# TSAL.net
KiCad netlist of a schematic drawn in Altium Designer
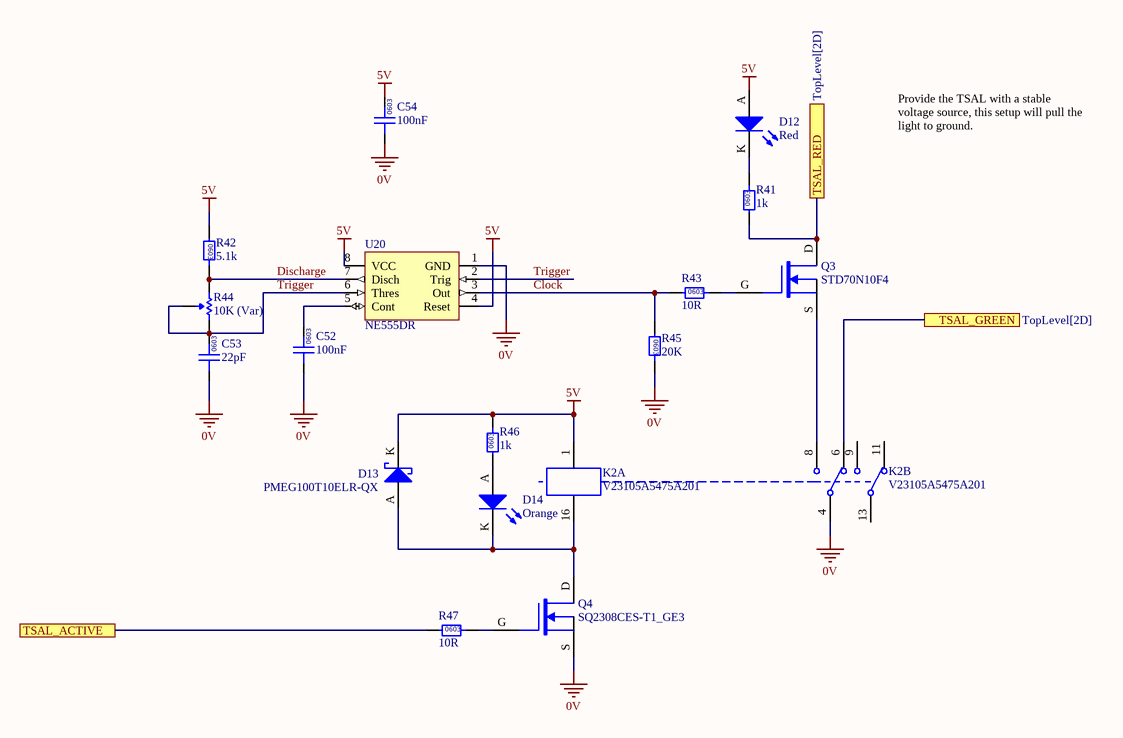
[diagram p0: TSAL.SchDoc]

(export (version "E")
  (design (tool "Eeschema 10.0.6"))
  (components
    (comp (ref "C52")
      (value "100nF")
      (footprint "0603")
      (fields
        (field (name "PART NUMBER") "GCM188L81H104KA57D")
        (field (name "MANUFACTURER") "muRata")
        (field (name "TOLERANCE") "±10%")
      )
      (libsource (lib "ts_standard_library") (part "Capacitor 0603"))
    )
    (comp (ref "C53")
      (value "22pF")
      (footprint "0603")
      (fields
        (field (name "PART NUMBER") "GRM0335C1H220JA01D")
        (field (name "MANUFACTURER") "Murata Electronics")
        (field (name "TOLERANCE") "±5%")
      )
      (libsource (lib "ts_standard_library") (part "Capacitor 0603"))
    )
    (comp (ref "C54")
      (value "100nF")
      (footprint "0603")
      (fields
        (field (name "PART NUMBER") "GCM188L81H104KA57D")
        (field (name "MANUFACTURER") "muRata")
        (field (name "TOLERANCE") "±10%")
      )
      (libsource (lib "ts_standard_library") (part "Capacitor 0603"))
    )
    (comp (ref "D12")
      (value "Red")
      (footprint "0805 LED")
      (description "Red LED Indication - Discrete 1.75V 0805 (2012 Metric)")
      (fields (field (name "PART NUMBER") "SML-210LTT86") (field (name "MANUFACTURER") "ROHM Semiconductor"))
      (libsource (lib "ts_standard_library") (part "LED"))
    )
    (comp (ref "D13")
      (value "PMEG100T10ELR-QX")
      (footprint "NXP SOD123W")
      (fields
        (field (name "MANUFACTURER") "Nexperia USA Inc.")
        (field (name "DIGIKEY PART NUMBER") "1727-PMEG100T10ELR-QXCT-ND")
      )
      (libsource (lib "ts_standard_library") (part "Diode (Schottky)"))
    )
    (comp (ref "D14")
      (value "Orange")
      (footprint "0805 LED")
      (description "Orange LED Indication - Discrete 1.75V 0805 (2012 Metric)")
      (fields (field (name "PART NUMBER") "SML-211DTT86") (field (name "MANUFACTURER") "ROHM Semiconductor"))
      (libsource (lib "ts_standard_library") (part "LED"))
    )
    (comp (ref "K2")
      (value "V23105A5475A201")
      (footprint "TI 2-DIL")
      (description "5V DPDT Relay 3A 220VDC")
      (libsource (lib "Team Swinburne") (part "Symbol"))
    )
    (comp (ref "Q3")
      (value "STD70N10F4")
      (footprint "STM TO-252 MOSFET")
      (description "N-Channel 100V 60A (Tc) 125W (Tc) Surface Mount DPAK")
      (fields
        (field (name "MANUFACTURER") "STMicroelectronics")
        (field (name "DIGIKEY PART NUMBER") "497-8806-2-ND")
        (field (name "PUBLISHER") "Altium Limited")
      )
      (libsource (lib "ts_standard_library") (part "MOSFET-N"))
    )
    (comp (ref "Q4")
      (value "SQ2308CES-T1_GE3")
      (footprint "VSHY SOT-23-3")
      (description "MOSFET N-CH 60V 2.3A SOT23")
      (fields
        (field (name "MANUFACTURER") "Vishay Siliconix")
        (field (name "DIGIKEY PART NUMBER") "SQ2308CES-T1_GE3CT-ND")
        (field (name "PUBLISHER") "Altium Limited")
      )
      (libsource (lib "ts_standard_library") (part "MOSFET-N"))
    )
    (comp (ref "R41")
      (value "1k")
      (footprint "0603")
      (fields
        (field (name "PART NUMBER") "RC0603FR-071KL")
        (field (name "MANUFACTURER") "YAGEO")
        (field (name "TOLERANCE") "0.01")
      )
      (libsource (lib "ts_standard_library") (part "Resistor 0603"))
    )
    (comp (ref "R42")
      (value "5.1k")
      (footprint "0603")
      (fields
        (field (name "PART NUMBER") "RC0603JR-075K1L")
        (field (name "MANUFACTURER") "YAGEO")
        (field (name "TOLERANCE") "0.01")
      )
      (libsource (lib "ts_standard_library") (part "Resistor 0603"))
    )
    (comp (ref "R43")
      (value "10R")
      (footprint "0603")
      (fields
        (field (name "PART NUMBER") "RC0603FR-0710RL")
        (field (name "MANUFACTURER") "YAGEO")
        (field (name "TOLERANCE") "0.01")
      )
      (libsource (lib "ts_standard_library") (part "Resistor 0603"))
    )
    (comp (ref "R44")
      (value "10K (Var)")
      (footprint "B 3296")
      (fields
        (field (name "PART NUMBER") "3296W-1-103LF")
        (field (name "MANUFACTURER") "Bournes Inc")
        (field (name "TOLERANCE") "0.1")
      )
      (libsource (lib "ts_standard_library") (part "Resistor (Potentiometer)"))
    )
    (comp (ref "R45")
      (value "20K")
      (footprint "0603")
      (fields
        (field (name "PART NUMBER") "RC0603FR-0720KL")
        (field (name "MANUFACTURER") "YAGEO")
        (field (name "TOLERANCE") "0.01")
      )
      (libsource (lib "ts_standard_library") (part "Resistor 0603"))
    )
    (comp (ref "R46")
      (value "1k")
      (footprint "0603")
      (fields
        (field (name "PART NUMBER") "RC0603FR-071KL")
        (field (name "MANUFACTURER") "YAGEO")
        (field (name "TOLERANCE") "0.01")
      )
      (libsource (lib "ts_standard_library") (part "Resistor 0603"))
    )
    (comp (ref "R47")
      (value "10R")
      (footprint "0603")
      (fields
        (field (name "PART NUMBER") "RC0603FR-0710RL")
        (field (name "MANUFACTURER") "YAGEO")
        (field (name "TOLERANCE") "0.01")
      )
      (libsource (lib "ts_standard_library") (part "Resistor 0603"))
    )
    (comp (ref "U20")
      (value "NE555DR")
      (footprint "TI 8-SOIC")
      (description "IC OSC SGL TIMER 100KHZ 8-SOIC")
      (libsource (lib "Team Swinburne") (part "NE555DR"))
    )
  )
  (nets
    (net (code "1") (name "/Clock") (class "Default")
      (node (ref "R43") (pin "1") (pinfunction "1_1") (pintype "passive"))
      (node (ref "R45") (pin "1") (pinfunction "1_1") (pintype "passive"))
      (node (ref "U20") (pin "3") (pinfunction "Out_3") (pintype "output"))
    )
    (net (code "2") (name "/Discharge") (class "Default")
      (node (ref "R42") (pin "2") (pinfunction "2_2") (pintype "passive"))
      (node (ref "R44") (pin "3") (pinfunction "CW_3") (pintype "passive"))
      (node (ref "U20") (pin "7") (pinfunction "Disch_7") (pintype "output"))
    )
    (net (code "3") (name "/TSAL_ACTIVE") (class "Default")
      (node (ref "R47") (pin "1") (pinfunction "1_1") (pintype "passive"))
    )
    (net (code "4") (name "/TSAL_GREEN") (class "Default")
      (node (ref "K2") (pin "6") (pinfunction "6_6") (pintype "passive"))
    )
    (net (code "5") (name "/TSAL_RED") (class "Default")
      (node (ref "Q3") (pin "D") (pinfunction "D_D") (pintype "passive"))
      (node (ref "R41") (pin "1") (pinfunction "1_1") (pintype "passive"))
    )
    (net (code "6") (name "/Trigger") (class "Default")
      (node (ref "C53") (pin "2") (pinfunction "2_2") (pintype "passive"))
      (node (ref "R44") (pin "1") (pinfunction "CCW_1") (pintype "passive"))
      (node (ref "R44") (pin "2") (pinfunction "Wiper_2") (pintype "passive"))
      (node (ref "U20") (pin "2") (pinfunction "Trig_2") (pintype "input"))
      (node (ref "U20") (pin "6") (pinfunction "Thres_6") (pintype "input"))
    )
    (net (code "7") (name "0V") (class "Default")
      (node (ref "C52") (pin "1") (pinfunction "1_1") (pintype "passive"))
      (node (ref "C53") (pin "1") (pinfunction "1_1") (pintype "passive"))
      (node (ref "C54") (pin "1") (pinfunction "1_1") (pintype "passive"))
      (node (ref "K2") (pin "4") (pinfunction "4_4") (pintype "passive"))
      (node (ref "Q4") (pin "S") (pinfunction "S_S") (pintype "passive"))
      (node (ref "R45") (pin "2") (pinfunction "2_2") (pintype "passive"))
      (node (ref "U20") (pin "1") (pinfunction "GND_1") (pintype "power_in"))
    )
    (net (code "8") (name "5V") (class "Default")
      (node (ref "C54") (pin "2") (pinfunction "2_2") (pintype "passive"))
      (node (ref "D12") (pin "A") (pinfunction "A_A") (pintype "passive"))
      (node (ref "D13") (pin "K") (pinfunction "K_K") (pintype "passive"))
      (node (ref "K2") (pin "1") (pinfunction "1_1") (pintype "passive"))
      (node (ref "R42") (pin "1") (pinfunction "1_1") (pintype "passive"))
      (node (ref "R46") (pin "2") (pinfunction "2_2") (pintype "passive"))
      (node (ref "U20") (pin "4") (pinfunction "Reset_4") (pintype "passive"))
      (node (ref "U20") (pin "8") (pinfunction "VCC_8") (pintype "passive"))
    )
    (net (code "9") (name "Net-(D12-PadK)") (class "Default")
      (node (ref "D12") (pin "K") (pinfunction "K_K") (pintype "passive"))
      (node (ref "R41") (pin "2") (pinfunction "2_2") (pintype "passive"))
    )
    (net (code "10") (name "Net-(D13-PadA)") (class "Default")
      (node (ref "D13") (pin "A") (pinfunction "A_A") (pintype "passive"))
      (node (ref "D14") (pin "K") (pinfunction "K_K") (pintype "passive"))
      (node (ref "K2") (pin "16") (pinfunction "16_16") (pintype "passive"))
      (node (ref "Q4") (pin "D") (pinfunction "D_D") (pintype "passive"))
    )
    (net (code "11") (name "Net-(D14-PadA)") (class "Default")
      (node (ref "D14") (pin "A") (pinfunction "A_A") (pintype "passive"))
      (node (ref "R46") (pin "1") (pinfunction "1_1") (pintype "passive"))
    )
    (net (code "12") (name "Net-(K2-Pad8)") (class "Default")
      (node (ref "K2") (pin "8") (pinfunction "8_8") (pintype "passive"))
      (node (ref "Q3") (pin "S") (pinfunction "S_S") (pintype "passive"))
    )
    (net (code "13") (name "Net-(Q3-PadG)") (class "Default")
      (node (ref "Q3") (pin "G") (pinfunction "G_G") (pintype "passive"))
      (node (ref "R43") (pin "2") (pinfunction "2_2") (pintype "passive"))
    )
    (net (code "14") (name "Net-(Q4-PadG)") (class "Default")
      (node (ref "Q4") (pin "G") (pinfunction "G_G") (pintype "passive"))
      (node (ref "R47") (pin "2") (pinfunction "2_2") (pintype "passive"))
    )
    (net (code "15") (name "Net-(U20-Cont)") (class "Default")
      (node (ref "C52") (pin "2") (pinfunction "2_2") (pintype "passive"))
      (node (ref "U20") (pin "5") (pinfunction "Cont_5") (pintype "bidirectional"))
    )
    (net (code "16") (name "unconnected-(K2-Pad9)") (class "Default")
      (node (ref "K2") (pin "9") (pinfunction "9_9") (pintype "passive"))
    )
    (net (code "17") (name "unconnected-(K2-Pad11)") (class "Default")
      (node (ref "K2") (pin "11") (pinfunction "11_11") (pintype "passive"))
    )
    (net (code "18") (name "unconnected-(K2-Pad13)") (class "Default")
      (node (ref "K2") (pin "13") (pinfunction "13_13") (pintype "passive"))
    )
  )
)
